# xr_vco_pots_V2.net
KiCad netlist of a schematic drawn in EAGLE
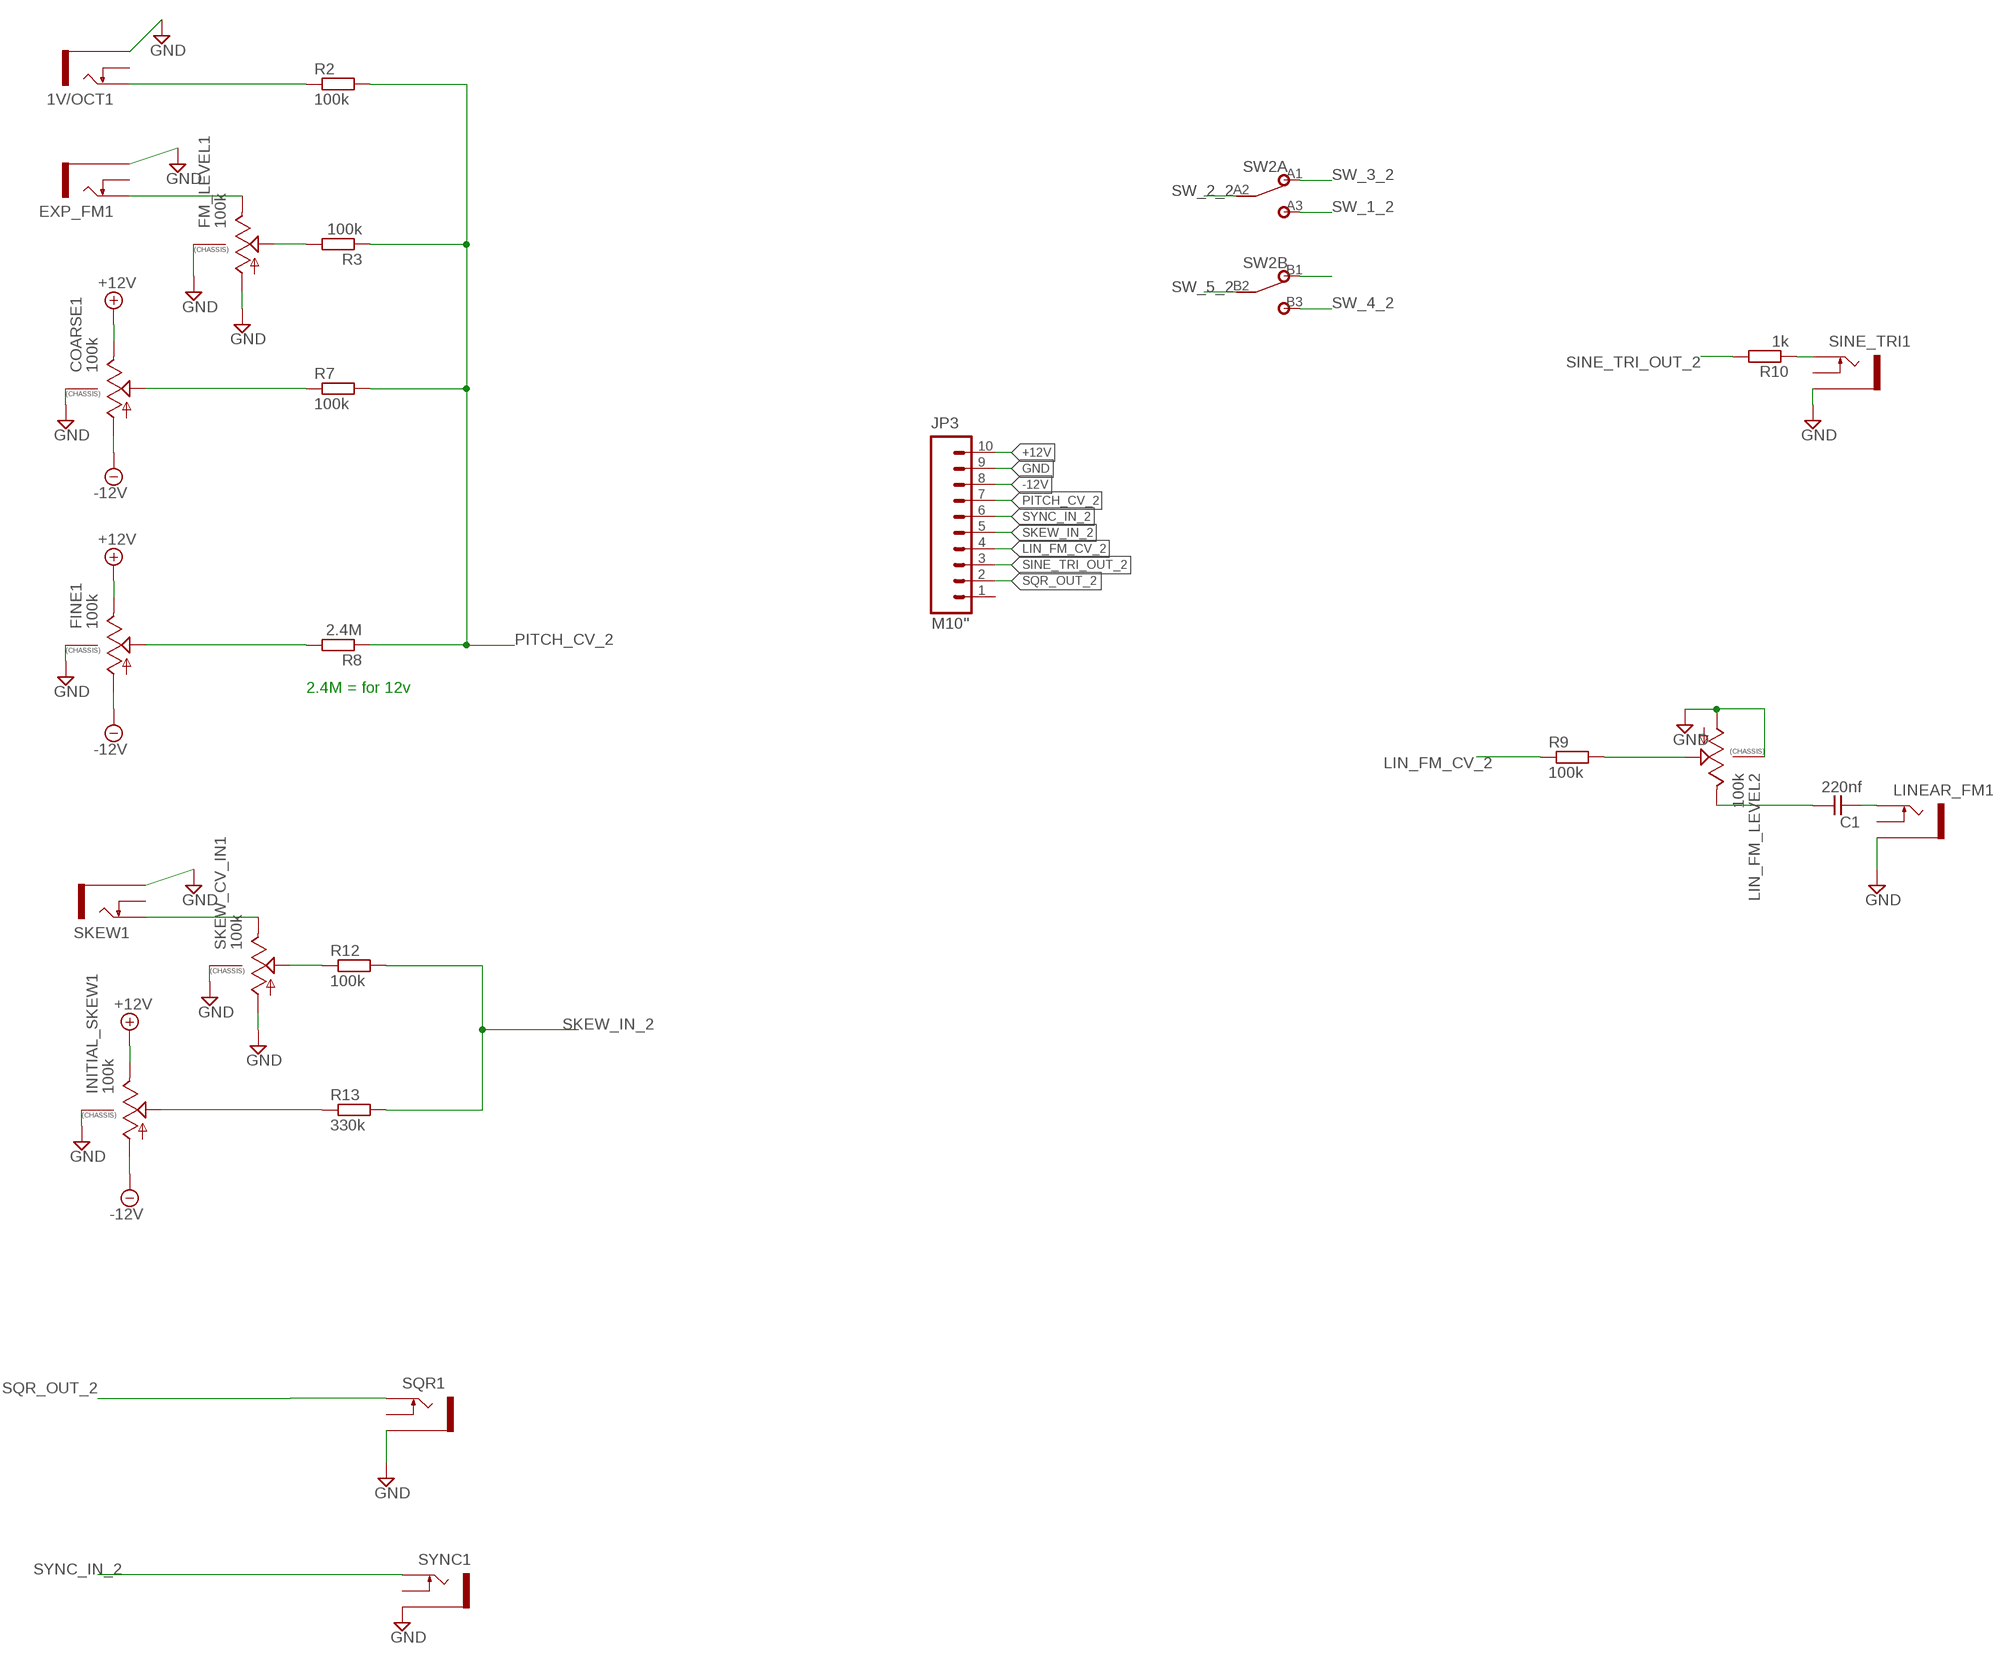
[diagram p0: schematic, sheet 1, part 1 of 2]
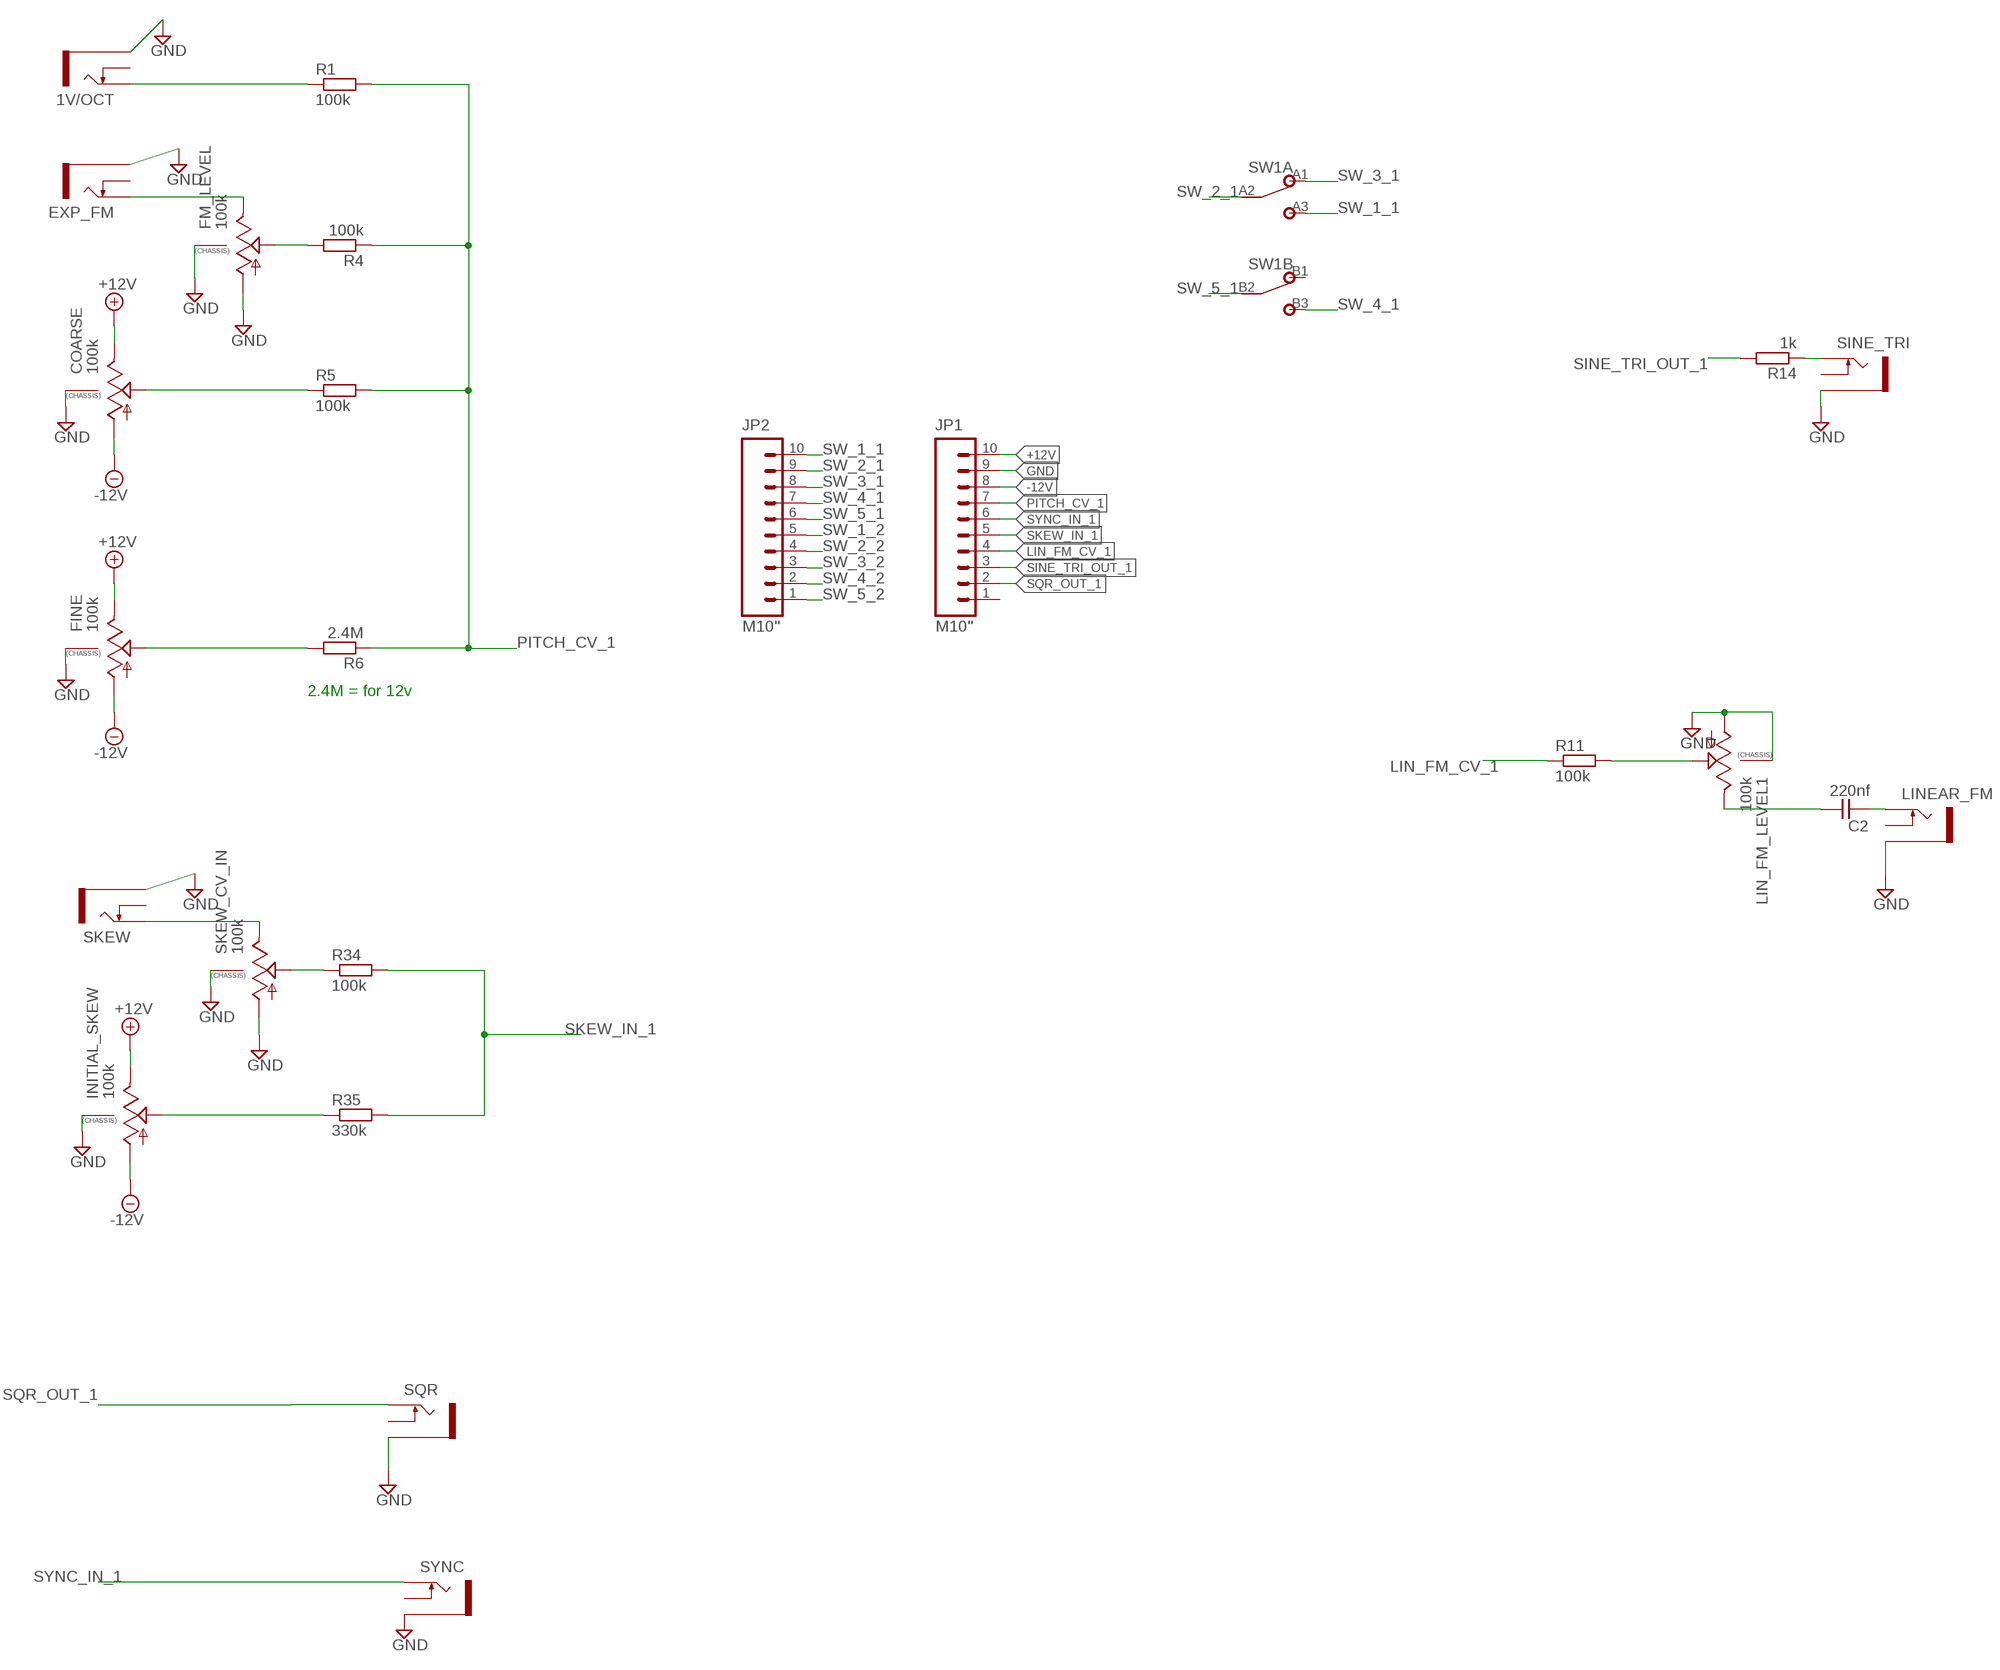
[diagram p1: schematic, sheet 1, part 2 of 2]

(export (version "E")
  (design (tool "Eeschema 10.0.6"))
  (components
    (comp (ref "1V/OCT")
      (value "THONKICONNNEW")
      (footprint "eagle-import:WQP-PJ301M-12_JACK")
      (libsource (lib "eagle-import") (part "THONKICONNNEW"))
    )
    (comp (ref "1V/OCT1")
      (value "THONKICONNNEW")
      (footprint "eagle-import:WQP-PJ301M-12_JACK")
      (libsource (lib "eagle-import") (part "THONKICONNNEW"))
    )
    (comp (ref "C1")
      (value "220nf")
      (footprint "eagle-import:C050-024X044")
      (libsource (lib "eagle-import") (part "C-EU050-024X044"))
    )
    (comp (ref "C2")
      (value "220nf")
      (footprint "eagle-import:C050-024X044")
      (libsource (lib "eagle-import") (part "C-EU050-024X044"))
    )
    (comp (ref "COARSE")
      (value "100k")
      (footprint "eagle-import:9MM_SNAP-IN_POT")
      (libsource (lib "eagle-import") (part "9MM_SNAP-IN_POT_CHASSIS"))
    )
    (comp (ref "COARSE1")
      (value "100k")
      (footprint "eagle-import:9MM_SNAP-IN_POT")
      (libsource (lib "eagle-import") (part "9MM_SNAP-IN_POT_CHASSIS"))
    )
    (comp (ref "EXP_FM")
      (value "THONKICONNNEW")
      (footprint "eagle-import:WQP-PJ301M-12_JACK")
      (libsource (lib "eagle-import") (part "THONKICONNNEW"))
    )
    (comp (ref "EXP_FM1")
      (value "THONKICONNNEW")
      (footprint "eagle-import:WQP-PJ301M-12_JACK")
      (libsource (lib "eagle-import") (part "THONKICONNNEW"))
    )
    (comp (ref "FINE")
      (value "100k")
      (footprint "eagle-import:9MM_SNAP-IN_POT")
      (libsource (lib "eagle-import") (part "9MM_SNAP-IN_POT_CHASSIS"))
    )
    (comp (ref "FINE1")
      (value "100k")
      (footprint "eagle-import:9MM_SNAP-IN_POT")
      (libsource (lib "eagle-import") (part "9MM_SNAP-IN_POT_CHASSIS"))
    )
    (comp (ref "FM_LEVEL")
      (value "100k")
      (footprint "eagle-import:9MM_SNAP-IN_POT")
      (libsource (lib "eagle-import") (part "9MM_SNAP-IN_POT_CHASSIS"))
    )
    (comp (ref "FM_LEVEL1")
      (value "100k")
      (footprint "eagle-import:9MM_SNAP-IN_POT")
      (libsource (lib "eagle-import") (part "9MM_SNAP-IN_POT_CHASSIS"))
    )
    (comp (ref "INITIAL_SKEW")
      (value "100k")
      (footprint "eagle-import:9MM_SNAP-IN_POT")
      (libsource (lib "eagle-import") (part "9MM_SNAP-IN_POT_CHASSIS"))
    )
    (comp (ref "INITIAL_SKEW1")
      (value "100k")
      (footprint "eagle-import:9MM_SNAP-IN_POT")
      (libsource (lib "eagle-import") (part "9MM_SNAP-IN_POT_CHASSIS"))
    )
    (comp (ref "JP1")
      (value "M10\"")
      (footprint "eagle-import:1X10")
      (libsource (lib "eagle-import") (part "M10{dblquote}"))
    )
    (comp (ref "JP2")
      (value "M10\"")
      (footprint "eagle-import:1X10")
      (libsource (lib "eagle-import") (part "M10{dblquote}"))
    )
    (comp (ref "JP3")
      (value "M10\"")
      (footprint "eagle-import:1X10")
      (libsource (lib "eagle-import") (part "M10{dblquote}"))
    )
    (comp (ref "LINEAR_FM")
      (value "THONKICONNNEW")
      (footprint "eagle-import:WQP-PJ301M-12_JACK")
      (libsource (lib "eagle-import") (part "THONKICONNNEW"))
    )
    (comp (ref "LINEAR_FM1")
      (value "THONKICONNNEW")
      (footprint "eagle-import:WQP-PJ301M-12_JACK")
      (libsource (lib "eagle-import") (part "THONKICONNNEW"))
    )
    (comp (ref "LIN_FM_LEVEL1")
      (value "100k")
      (footprint "eagle-import:9MM_SNAP-IN_POT")
      (libsource (lib "eagle-import") (part "9MM_SNAP-IN_POT_CHASSIS"))
    )
    (comp (ref "LIN_FM_LEVEL2")
      (value "100k")
      (footprint "eagle-import:9MM_SNAP-IN_POT")
      (libsource (lib "eagle-import") (part "9MM_SNAP-IN_POT_CHASSIS"))
    )
    (comp (ref "R1")
      (value "100k")
      (footprint "eagle-import:7MM_RESISTOR")
      (libsource (lib "eagle-import") (part "RESISTOR7MM"))
    )
    (comp (ref "R2")
      (value "100k")
      (footprint "eagle-import:7MM_RESISTOR")
      (libsource (lib "eagle-import") (part "RESISTOR7MM"))
    )
    (comp (ref "R3")
      (value "100k")
      (footprint "eagle-import:7MM_RESISTOR")
      (libsource (lib "eagle-import") (part "RESISTOR7MM"))
    )
    (comp (ref "R4")
      (value "100k")
      (footprint "eagle-import:7MM_RESISTOR")
      (libsource (lib "eagle-import") (part "RESISTOR7MM"))
    )
    (comp (ref "R5")
      (value "100k")
      (footprint "eagle-import:7MM_RESISTOR")
      (libsource (lib "eagle-import") (part "RESISTOR7MM"))
    )
    (comp (ref "R6")
      (value "2.4M")
      (footprint "eagle-import:7MM_RESISTOR")
      (libsource (lib "eagle-import") (part "RESISTOR7MM"))
    )
    (comp (ref "R7")
      (value "100k")
      (footprint "eagle-import:7MM_RESISTOR")
      (libsource (lib "eagle-import") (part "RESISTOR7MM"))
    )
    (comp (ref "R8")
      (value "2.4M")
      (footprint "eagle-import:7MM_RESISTOR")
      (libsource (lib "eagle-import") (part "RESISTOR7MM"))
    )
    (comp (ref "R9")
      (value "100k")
      (footprint "eagle-import:7MM_RESISTOR")
      (libsource (lib "eagle-import") (part "RESISTOR7MM"))
    )
    (comp (ref "R10")
      (value "1k")
      (footprint "eagle-import:7MM_RESISTOR")
      (libsource (lib "eagle-import") (part "RESISTOR7MM"))
    )
    (comp (ref "R11")
      (value "100k")
      (footprint "eagle-import:7MM_RESISTOR")
      (libsource (lib "eagle-import") (part "RESISTOR7MM"))
    )
    (comp (ref "R12")
      (value "100k")
      (footprint "eagle-import:7MM_RESISTOR")
      (libsource (lib "eagle-import") (part "RESISTOR7MM"))
    )
    (comp (ref "R13")
      (value "330k")
      (footprint "eagle-import:7MM_RESISTOR")
      (libsource (lib "eagle-import") (part "RESISTOR7MM"))
    )
    (comp (ref "R14")
      (value "1k")
      (footprint "eagle-import:7MM_RESISTOR")
      (libsource (lib "eagle-import") (part "RESISTOR7MM"))
    )
    (comp (ref "R34")
      (value "100k")
      (footprint "eagle-import:7MM_RESISTOR")
      (libsource (lib "eagle-import") (part "RESISTOR7MM"))
    )
    (comp (ref "R35")
      (value "330k")
      (footprint "eagle-import:7MM_RESISTOR")
      (libsource (lib "eagle-import") (part "RESISTOR7MM"))
    )
    (comp (ref "SINE_TRI")
      (value "THONKICONNNEW")
      (footprint "eagle-import:WQP-PJ301M-12_JACK")
      (libsource (lib "eagle-import") (part "THONKICONNNEW"))
    )
    (comp (ref "SINE_TRI1")
      (value "THONKICONNNEW")
      (footprint "eagle-import:WQP-PJ301M-12_JACK")
      (libsource (lib "eagle-import") (part "THONKICONNNEW"))
    )
    (comp (ref "SKEW")
      (value "THONKICONNNEW")
      (footprint "eagle-import:WQP-PJ301M-12_JACK")
      (libsource (lib "eagle-import") (part "THONKICONNNEW"))
    )
    (comp (ref "SKEW1")
      (value "THONKICONNNEW")
      (footprint "eagle-import:WQP-PJ301M-12_JACK")
      (libsource (lib "eagle-import") (part "THONKICONNNEW"))
    )
    (comp (ref "SKEW_CV_IN")
      (value "100k")
      (footprint "eagle-import:9MM_SNAP-IN_POT")
      (libsource (lib "eagle-import") (part "9MM_SNAP-IN_POT_CHASSIS"))
    )
    (comp (ref "SKEW_CV_IN1")
      (value "100k")
      (footprint "eagle-import:9MM_SNAP-IN_POT")
      (libsource (lib "eagle-import") (part "9MM_SNAP-IN_POT_CHASSIS"))
    )
    (comp (ref "SQR")
      (value "THONKICONNNEW")
      (footprint "eagle-import:WQP-PJ301M-12_JACK")
      (libsource (lib "eagle-import") (part "THONKICONNNEW"))
    )
    (comp (ref "SQR1")
      (value "THONKICONNNEW")
      (footprint "eagle-import:WQP-PJ301M-12_JACK")
      (libsource (lib "eagle-import") (part "THONKICONNNEW"))
    )
    (comp (ref "SW1")
      (value "DPDT")
      (footprint "eagle-import:DPDT")
      (libsource (lib "eagle-import") (part "DPDT"))
    )
    (comp (ref "SW2")
      (value "DPDT")
      (footprint "eagle-import:DPDT")
      (libsource (lib "eagle-import") (part "DPDT"))
    )
    (comp (ref "SYNC")
      (value "THONKICONNNEW")
      (footprint "eagle-import:WQP-PJ301M-12_JACK")
      (libsource (lib "eagle-import") (part "THONKICONNNEW"))
    )
    (comp (ref "SYNC1")
      (value "THONKICONNNEW")
      (footprint "eagle-import:WQP-PJ301M-12_JACK")
      (libsource (lib "eagle-import") (part "THONKICONNNEW"))
    )
  )
  (nets
    (net (code "1") (name "+12V") (class "Default")
      (node (ref "COARSE") (pin "3") (pinfunction "E_3") (pintype "passive"))
      (node (ref "COARSE1") (pin "3") (pinfunction "E_3") (pintype "passive"))
      (node (ref "FINE") (pin "3") (pinfunction "E_3") (pintype "passive"))
      (node (ref "FINE1") (pin "3") (pinfunction "E_3") (pintype "passive"))
      (node (ref "INITIAL_SKEW") (pin "3") (pinfunction "E_3") (pintype "passive"))
      (node (ref "INITIAL_SKEW1") (pin "3") (pinfunction "E_3") (pintype "passive"))
      (node (ref "JP1") (pin "10") (pinfunction "10_10") (pintype "passive"))
      (node (ref "JP3") (pin "10") (pinfunction "10_10") (pintype "passive"))
    )
    (net (code "2") (name "-12V") (class "Default")
      (node (ref "COARSE") (pin "1") (pinfunction "A_1") (pintype "passive"))
      (node (ref "COARSE1") (pin "1") (pinfunction "A_1") (pintype "passive"))
      (node (ref "FINE") (pin "1") (pinfunction "A_1") (pintype "passive"))
      (node (ref "FINE1") (pin "1") (pinfunction "A_1") (pintype "passive"))
      (node (ref "INITIAL_SKEW") (pin "1") (pinfunction "A_1") (pintype "passive"))
      (node (ref "INITIAL_SKEW1") (pin "1") (pinfunction "A_1") (pintype "passive"))
      (node (ref "JP1") (pin "8") (pinfunction "8_8") (pintype "passive"))
      (node (ref "JP3") (pin "8") (pinfunction "8_8") (pintype "passive"))
    )
    (net (code "3") (name "/SW_1_1") (class "Default")
      (node (ref "JP2") (pin "10") (pinfunction "10_10") (pintype "passive"))
      (node (ref "SW1") (pin "A3") (pinfunction "3_A3") (pintype "passive"))
    )
    (net (code "4") (name "/SW_1_2") (class "Default")
      (node (ref "JP2") (pin "5") (pinfunction "5_5") (pintype "passive"))
      (node (ref "SW2") (pin "A3") (pinfunction "3_A3") (pintype "passive"))
    )
    (net (code "5") (name "/SW_2_1") (class "Default")
      (node (ref "JP2") (pin "9") (pinfunction "9_9") (pintype "passive"))
      (node (ref "SW1") (pin "A2") (pinfunction "2_A2") (pintype "passive"))
    )
    (net (code "6") (name "/SW_2_2") (class "Default")
      (node (ref "JP2") (pin "4") (pinfunction "4_4") (pintype "passive"))
      (node (ref "SW2") (pin "A2") (pinfunction "2_A2") (pintype "passive"))
    )
    (net (code "7") (name "/SW_3_1") (class "Default")
      (node (ref "JP2") (pin "8") (pinfunction "8_8") (pintype "passive"))
      (node (ref "SW1") (pin "A1") (pinfunction "1_A1") (pintype "passive"))
    )
    (net (code "8") (name "/SW_3_2") (class "Default")
      (node (ref "JP2") (pin "3") (pinfunction "3_3") (pintype "passive"))
      (node (ref "SW2") (pin "A1") (pinfunction "1_A1") (pintype "passive"))
    )
    (net (code "9") (name "/SW_4_1") (class "Default")
      (node (ref "JP2") (pin "7") (pinfunction "7_7") (pintype "passive"))
      (node (ref "SW1") (pin "B3") (pinfunction "3_B3") (pintype "passive"))
    )
    (net (code "10") (name "/SW_4_2") (class "Default")
      (node (ref "JP2") (pin "2") (pinfunction "2_2") (pintype "passive"))
      (node (ref "SW2") (pin "B3") (pinfunction "3_B3") (pintype "passive"))
    )
    (net (code "11") (name "/SW_5_1") (class "Default")
      (node (ref "JP2") (pin "6") (pinfunction "6_6") (pintype "passive"))
      (node (ref "SW1") (pin "B2") (pinfunction "2_B2") (pintype "passive"))
    )
    (net (code "12") (name "/SW_5_2") (class "Default")
      (node (ref "JP2") (pin "1") (pinfunction "1_1") (pintype "passive"))
      (node (ref "SW2") (pin "B2") (pinfunction "2_B2") (pintype "passive"))
    )
    (net (code "13") (name "GND") (class "Default")
      (node (ref "1V/OCT") (pin "P$3_SLEEVE") (pinfunction "SLEEVE_P$3_SLEEVE") (pintype "passive"))
      (node (ref "1V/OCT1") (pin "P$3_SLEEVE") (pinfunction "SLEEVE_P$3_SLEEVE") (pintype "passive"))
      (node (ref "COARSE") (pin "CHASSIS2") (pinfunction "P$1_CHASSIS2") (pintype "passive"))
      (node (ref "COARSE1") (pin "CHASSIS2") (pinfunction "P$1_CHASSIS2") (pintype "passive"))
      (node (ref "EXP_FM") (pin "P$3_SLEEVE") (pinfunction "SLEEVE_P$3_SLEEVE") (pintype "passive"))
      (node (ref "EXP_FM1") (pin "P$3_SLEEVE") (pinfunction "SLEEVE_P$3_SLEEVE") (pintype "passive"))
      (node (ref "FINE") (pin "CHASSIS2") (pinfunction "P$1_CHASSIS2") (pintype "passive"))
      (node (ref "FINE1") (pin "CHASSIS2") (pinfunction "P$1_CHASSIS2") (pintype "passive"))
      (node (ref "FM_LEVEL") (pin "1") (pinfunction "A_1") (pintype "passive"))
      (node (ref "FM_LEVEL") (pin "CHASSIS2") (pinfunction "P$1_CHASSIS2") (pintype "passive"))
      (node (ref "FM_LEVEL1") (pin "1") (pinfunction "A_1") (pintype "passive"))
      (node (ref "FM_LEVEL1") (pin "CHASSIS2") (pinfunction "P$1_CHASSIS2") (pintype "passive"))
      (node (ref "INITIAL_SKEW") (pin "CHASSIS2") (pinfunction "P$1_CHASSIS2") (pintype "passive"))
      (node (ref "INITIAL_SKEW1") (pin "CHASSIS2") (pinfunction "P$1_CHASSIS2") (pintype "passive"))
      (node (ref "JP1") (pin "9") (pinfunction "9_9") (pintype "passive"))
      (node (ref "JP3") (pin "9") (pinfunction "9_9") (pintype "passive"))
      (node (ref "LINEAR_FM") (pin "P$3_SLEEVE") (pinfunction "SLEEVE_P$3_SLEEVE") (pintype "passive"))
      (node (ref "LINEAR_FM1") (pin "P$3_SLEEVE") (pinfunction "SLEEVE_P$3_SLEEVE") (pintype "passive"))
      (node (ref "LIN_FM_LEVEL1") (pin "1") (pinfunction "A_1") (pintype "passive"))
      (node (ref "LIN_FM_LEVEL1") (pin "CHASSIS2") (pinfunction "P$1_CHASSIS2") (pintype "passive"))
      (node (ref "LIN_FM_LEVEL2") (pin "1") (pinfunction "A_1") (pintype "passive"))
      (node (ref "LIN_FM_LEVEL2") (pin "CHASSIS2") (pinfunction "P$1_CHASSIS2") (pintype "passive"))
      (node (ref "SINE_TRI") (pin "P$3_SLEEVE") (pinfunction "SLEEVE_P$3_SLEEVE") (pintype "passive"))
      (node (ref "SINE_TRI1") (pin "P$3_SLEEVE") (pinfunction "SLEEVE_P$3_SLEEVE") (pintype "passive"))
      (node (ref "SKEW") (pin "P$3_SLEEVE") (pinfunction "SLEEVE_P$3_SLEEVE") (pintype "passive"))
      (node (ref "SKEW1") (pin "P$3_SLEEVE") (pinfunction "SLEEVE_P$3_SLEEVE") (pintype "passive"))
      (node (ref "SKEW_CV_IN") (pin "1") (pinfunction "A_1") (pintype "passive"))
      (node (ref "SKEW_CV_IN") (pin "CHASSIS2") (pinfunction "P$1_CHASSIS2") (pintype "passive"))
      (node (ref "SKEW_CV_IN1") (pin "1") (pinfunction "A_1") (pintype "passive"))
      (node (ref "SKEW_CV_IN1") (pin "CHASSIS2") (pinfunction "P$1_CHASSIS2") (pintype "passive"))
      (node (ref "SQR") (pin "P$3_SLEEVE") (pinfunction "SLEEVE_P$3_SLEEVE") (pintype "passive"))
      (node (ref "SQR1") (pin "P$3_SLEEVE") (pinfunction "SLEEVE_P$3_SLEEVE") (pintype "passive"))
      (node (ref "SYNC") (pin "P$3_SLEEVE") (pinfunction "SLEEVE_P$3_SLEEVE") (pintype "passive"))
      (node (ref "SYNC1") (pin "P$3_SLEEVE") (pinfunction "SLEEVE_P$3_SLEEVE") (pintype "passive"))
    )
    (net (code "14") (name "LIN_FM_CV_1") (class "Default")
      (node (ref "JP1") (pin "4") (pinfunction "4_4") (pintype "passive"))
      (node (ref "R11") (pin "1") (pinfunction "1_1") (pintype "passive"))
    )
    (net (code "15") (name "LIN_FM_CV_2") (class "Default")
      (node (ref "JP3") (pin "4") (pinfunction "4_4") (pintype "passive"))
      (node (ref "R9") (pin "1") (pinfunction "1_1") (pintype "passive"))
    )
    (net (code "16") (name "Net-(1V/OCT-TIP)") (class "Default")
      (node (ref "1V/OCT") (pin "P$1_TIP") (pinfunction "TIP_P$1_TIP") (pintype "passive"))
      (node (ref "R1") (pin "1") (pinfunction "1_1") (pintype "passive"))
    )
    (net (code "17") (name "Net-(1V/OCT1-TIP)") (class "Default")
      (node (ref "1V/OCT1") (pin "P$1_TIP") (pinfunction "TIP_P$1_TIP") (pintype "passive"))
      (node (ref "R2") (pin "1") (pinfunction "1_1") (pintype "passive"))
    )
    (net (code "18") (name "Net-(COARSE-S)") (class "Default")
      (node (ref "COARSE") (pin "2") (pinfunction "S_2") (pintype "passive"))
      (node (ref "R5") (pin "1") (pinfunction "1_1") (pintype "passive"))
    )
    (net (code "19") (name "Net-(COARSE1-S)") (class "Default")
      (node (ref "COARSE1") (pin "2") (pinfunction "S_2") (pintype "passive"))
      (node (ref "R7") (pin "1") (pinfunction "1_1") (pintype "passive"))
    )
    (net (code "20") (name "Net-(EXP_FM-TIP)") (class "Default")
      (node (ref "EXP_FM") (pin "P$1_TIP") (pinfunction "TIP_P$1_TIP") (pintype "passive"))
      (node (ref "FM_LEVEL") (pin "3") (pinfunction "E_3") (pintype "passive"))
    )
    (net (code "21") (name "Net-(EXP_FM1-TIP)") (class "Default")
      (node (ref "EXP_FM1") (pin "P$1_TIP") (pinfunction "TIP_P$1_TIP") (pintype "passive"))
      (node (ref "FM_LEVEL1") (pin "3") (pinfunction "E_3") (pintype "passive"))
    )
    (net (code "22") (name "Net-(FINE-S)") (class "Default")
      (node (ref "FINE") (pin "2") (pinfunction "S_2") (pintype "passive"))
      (node (ref "R6") (pin "2") (pinfunction "2_2") (pintype "passive"))
    )
    (net (code "23") (name "Net-(FINE1-S)") (class "Default")
      (node (ref "FINE1") (pin "2") (pinfunction "S_2") (pintype "passive"))
      (node (ref "R8") (pin "2") (pinfunction "2_2") (pintype "passive"))
    )
    (net (code "24") (name "Net-(FM_LEVEL-S)") (class "Default")
      (node (ref "FM_LEVEL") (pin "2") (pinfunction "S_2") (pintype "passive"))
      (node (ref "R4") (pin "2") (pinfunction "2_2") (pintype "passive"))
    )
    (net (code "25") (name "Net-(FM_LEVEL1-S)") (class "Default")
      (node (ref "FM_LEVEL1") (pin "2") (pinfunction "S_2") (pintype "passive"))
      (node (ref "R3") (pin "2") (pinfunction "2_2") (pintype "passive"))
    )
    (net (code "26") (name "Net-(INITIAL_SKEW-S)") (class "Default")
      (node (ref "INITIAL_SKEW") (pin "2") (pinfunction "S_2") (pintype "passive"))
      (node (ref "R35") (pin "1") (pinfunction "1_1") (pintype "passive"))
    )
    (net (code "27") (name "Net-(INITIAL_SKEW1-S)") (class "Default")
      (node (ref "INITIAL_SKEW1") (pin "2") (pinfunction "S_2") (pintype "passive"))
      (node (ref "R13") (pin "1") (pinfunction "1_1") (pintype "passive"))
    )
    (net (code "28") (name "Net-(LINEAR_FM-TIP)") (class "Default")
      (node (ref "C2") (pin "2") (pinfunction "2_2") (pintype "passive"))
      (node (ref "LINEAR_FM") (pin "P$1_TIP") (pinfunction "TIP_P$1_TIP") (pintype "passive"))
    )
    (net (code "29") (name "Net-(LINEAR_FM1-TIP)") (class "Default")
      (node (ref "C1") (pin "2") (pinfunction "2_2") (pintype "passive"))
      (node (ref "LINEAR_FM1") (pin "P$1_TIP") (pinfunction "TIP_P$1_TIP") (pintype "passive"))
    )
    (net (code "30") (name "Net-(LIN_FM_LEVEL1-E)") (class "Default")
      (node (ref "C2") (pin "1") (pinfunction "1_1") (pintype "passive"))
      (node (ref "LIN_FM_LEVEL1") (pin "3") (pinfunction "E_3") (pintype "passive"))
    )
    (net (code "31") (name "Net-(LIN_FM_LEVEL1-S)") (class "Default")
      (node (ref "LIN_FM_LEVEL1") (pin "2") (pinfunction "S_2") (pintype "passive"))
      (node (ref "R11") (pin "2") (pinfunction "2_2") (pintype "passive"))
    )
    (net (code "32") (name "Net-(LIN_FM_LEVEL2-E)") (class "Default")
      (node (ref "C1") (pin "1") (pinfunction "1_1") (pintype "passive"))
      (node (ref "LIN_FM_LEVEL2") (pin "3") (pinfunction "E_3") (pintype "passive"))
    )
    (net (code "33") (name "Net-(LIN_FM_LEVEL2-S)") (class "Default")
      (node (ref "LIN_FM_LEVEL2") (pin "2") (pinfunction "S_2") (pintype "passive"))
      (node (ref "R9") (pin "2") (pinfunction "2_2") (pintype "passive"))
    )
    (net (code "34") (name "Net-(SINE_TRI-TIP)") (class "Default")
      (node (ref "R14") (pin "1") (pinfunction "1_1") (pintype "passive"))
      (node (ref "SINE_TRI") (pin "P$1_TIP") (pinfunction "TIP_P$1_TIP") (pintype "passive"))
    )
    (net (code "35") (name "Net-(SINE_TRI1-TIP)") (class "Default")
      (node (ref "R10") (pin "1") (pinfunction "1_1") (pintype "passive"))
      (node (ref "SINE_TRI1") (pin "P$1_TIP") (pinfunction "TIP_P$1_TIP") (pintype "passive"))
    )
    (net (code "36") (name "Net-(SKEW-TIP)") (class "Default")
      (node (ref "SKEW") (pin "P$1_TIP") (pinfunction "TIP_P$1_TIP") (pintype "passive"))
      (node (ref "SKEW_CV_IN") (pin "3") (pinfunction "E_3") (pintype "passive"))
    )
    (net (code "37") (name "Net-(SKEW1-TIP)") (class "Default")
      (node (ref "SKEW1") (pin "P$1_TIP") (pinfunction "TIP_P$1_TIP") (pintype "passive"))
      (node (ref "SKEW_CV_IN1") (pin "3") (pinfunction "E_3") (pintype "passive"))
    )
    (net (code "38") (name "Net-(SKEW_CV_IN-S)") (class "Default")
      (node (ref "R34") (pin "1") (pinfunction "1_1") (pintype "passive"))
      (node (ref "SKEW_CV_IN") (pin "2") (pinfunction "S_2") (pintype "passive"))
    )
    (net (code "39") (name "Net-(SKEW_CV_IN1-S)") (class "Default")
      (node (ref "R12") (pin "1") (pinfunction "1_1") (pintype "passive"))
      (node (ref "SKEW_CV_IN1") (pin "2") (pinfunction "S_2") (pintype "passive"))
    )
    (net (code "40") (name "PITCH_CV_1") (class "Default")
      (node (ref "JP1") (pin "7") (pinfunction "7_7") (pintype "passive"))
      (node (ref "R1") (pin "2") (pinfunction "2_2") (pintype "passive"))
      (node (ref "R4") (pin "1") (pinfunction "1_1") (pintype "passive"))
      (node (ref "R5") (pin "2") (pinfunction "2_2") (pintype "passive"))
      (node (ref "R6") (pin "1") (pinfunction "1_1") (pintype "passive"))
    )
    (net (code "41") (name "PITCH_CV_2") (class "Default")
      (node (ref "JP3") (pin "7") (pinfunction "7_7") (pintype "passive"))
      (node (ref "R2") (pin "2") (pinfunction "2_2") (pintype "passive"))
      (node (ref "R3") (pin "1") (pinfunction "1_1") (pintype "passive"))
      (node (ref "R7") (pin "2") (pinfunction "2_2") (pintype "passive"))
      (node (ref "R8") (pin "1") (pinfunction "1_1") (pintype "passive"))
    )
    (net (code "42") (name "SINE_TRI_OUT_1") (class "Default")
      (node (ref "JP1") (pin "3") (pinfunction "3_3") (pintype "passive"))
      (node (ref "R14") (pin "2") (pinfunction "2_2") (pintype "passive"))
    )
    (net (code "43") (name "SINE_TRI_OUT_2") (class "Default")
      (node (ref "JP3") (pin "3") (pinfunction "3_3") (pintype "passive"))
      (node (ref "R10") (pin "2") (pinfunction "2_2") (pintype "passive"))
    )
    (net (code "44") (name "SKEW_IN_1") (class "Default")
      (node (ref "JP1") (pin "5") (pinfunction "5_5") (pintype "passive"))
      (node (ref "R34") (pin "2") (pinfunction "2_2") (pintype "passive"))
      (node (ref "R35") (pin "2") (pinfunction "2_2") (pintype "passive"))
    )
    (net (code "45") (name "SKEW_IN_2") (class "Default")
      (node (ref "JP3") (pin "5") (pinfunction "5_5") (pintype "passive"))
      (node (ref "R12") (pin "2") (pinfunction "2_2") (pintype "passive"))
      (node (ref "R13") (pin "2") (pinfunction "2_2") (pintype "passive"))
    )
    (net (code "46") (name "SQR_OUT_1") (class "Default")
      (node (ref "JP1") (pin "2") (pinfunction "2_2") (pintype "passive"))
      (node (ref "SQR") (pin "P$1_TIP") (pinfunction "TIP_P$1_TIP") (pintype "passive"))
    )
    (net (code "47") (name "SQR_OUT_2") (class "Default")
      (node (ref "JP3") (pin "2") (pinfunction "2_2") (pintype "passive"))
      (node (ref "SQR1") (pin "P$1_TIP") (pinfunction "TIP_P$1_TIP") (pintype "passive"))
    )
    (net (code "48") (name "SYNC_IN_1") (class "Default")
      (node (ref "JP1") (pin "6") (pinfunction "6_6") (pintype "passive"))
      (node (ref "SYNC") (pin "P$1_TIP") (pinfunction "TIP_P$1_TIP") (pintype "passive"))
    )
    (net (code "49") (name "SYNC_IN_2") (class "Default")
      (node (ref "JP3") (pin "6") (pinfunction "6_6") (pintype "passive"))
      (node (ref "SYNC1") (pin "P$1_TIP") (pinfunction "TIP_P$1_TIP") (pintype "passive"))
    )
    (net (code "50") (name "unconnected-(1V/OCT-SWITCH-PadP$2_SWITCH)") (class "Default")
      (node (ref "1V/OCT") (pin "P$2_SWITCH") (pinfunction "SWITCH_P$2_SWITCH") (pintype "passive"))
    )
    (net (code "51") (name "unconnected-(1V/OCT1-SWITCH-PadP$2_SWITCH)") (class "Default")
      (node (ref "1V/OCT1") (pin "P$2_SWITCH") (pinfunction "SWITCH_P$2_SWITCH") (pintype "passive"))
    )
    (net (code "52") (name "unconnected-(EXP_FM-SWITCH-PadP$2_SWITCH)") (class "Default")
      (node (ref "EXP_FM") (pin "P$2_SWITCH") (pinfunction "SWITCH_P$2_SWITCH") (pintype "passive"))
    )
    (net (code "53") (name "unconnected-(EXP_FM1-SWITCH-PadP$2_SWITCH)") (class "Default")
      (node (ref "EXP_FM1") (pin "P$2_SWITCH") (pinfunction "SWITCH_P$2_SWITCH") (pintype "passive"))
    )
    (net (code "54") (name "unconnected-(JP1-Pad1)") (class "Default")
      (node (ref "JP1") (pin "1") (pinfunction "1_1") (pintype "passive"))
    )
    (net (code "55") (name "unconnected-(JP3-Pad1)") (class "Default")
      (node (ref "JP3") (pin "1") (pinfunction "1_1") (pintype "passive"))
    )
    (net (code "56") (name "unconnected-(LINEAR_FM-SWITCH-PadP$2_SWITCH)") (class "Default")
      (node (ref "LINEAR_FM") (pin "P$2_SWITCH") (pinfunction "SWITCH_P$2_SWITCH") (pintype "passive"))
    )
    (net (code "57") (name "unconnected-(LINEAR_FM1-SWITCH-PadP$2_SWITCH)") (class "Default")
      (node (ref "LINEAR_FM1") (pin "P$2_SWITCH") (pinfunction "SWITCH_P$2_SWITCH") (pintype "passive"))
    )
    (net (code "58") (name "unconnected-(SINE_TRI-SWITCH-PadP$2_SWITCH)") (class "Default")
      (node (ref "SINE_TRI") (pin "P$2_SWITCH") (pinfunction "SWITCH_P$2_SWITCH") (pintype "passive"))
    )
    (net (code "59") (name "unconnected-(SINE_TRI1-SWITCH-PadP$2_SWITCH)") (class "Default")
      (node (ref "SINE_TRI1") (pin "P$2_SWITCH") (pinfunction "SWITCH_P$2_SWITCH") (pintype "passive"))
    )
    (net (code "60") (name "unconnected-(SKEW-SWITCH-PadP$2_SWITCH)") (class "Default")
      (node (ref "SKEW") (pin "P$2_SWITCH") (pinfunction "SWITCH_P$2_SWITCH") (pintype "passive"))
    )
    (net (code "61") (name "unconnected-(SKEW1-SWITCH-PadP$2_SWITCH)") (class "Default")
      (node (ref "SKEW1") (pin "P$2_SWITCH") (pinfunction "SWITCH_P$2_SWITCH") (pintype "passive"))
    )
    (net (code "62") (name "unconnected-(SQR-SWITCH-PadP$2_SWITCH)") (class "Default")
      (node (ref "SQR") (pin "P$2_SWITCH") (pinfunction "SWITCH_P$2_SWITCH") (pintype "passive"))
    )
    (net (code "63") (name "unconnected-(SQR1-SWITCH-PadP$2_SWITCH)") (class "Default")
      (node (ref "SQR1") (pin "P$2_SWITCH") (pinfunction "SWITCH_P$2_SWITCH") (pintype "passive"))
    )
    (net (code "64") (name "unconnected-(SW1B-1-PadB1)") (class "Default")
      (node (ref "SW1") (pin "B1") (pinfunction "1_B1") (pintype "passive"))
    )
    (net (code "65") (name "unconnected-(SW2B-1-PadB1)") (class "Default")
      (node (ref "SW2") (pin "B1") (pinfunction "1_B1") (pintype "passive"))
    )
    (net (code "66") (name "unconnected-(SYNC-SWITCH-PadP$2_SWITCH)") (class "Default")
      (node (ref "SYNC") (pin "P$2_SWITCH") (pinfunction "SWITCH_P$2_SWITCH") (pintype "passive"))
    )
    (net (code "67") (name "unconnected-(SYNC1-SWITCH-PadP$2_SWITCH)") (class "Default")
      (node (ref "SYNC1") (pin "P$2_SWITCH") (pinfunction "SWITCH_P$2_SWITCH") (pintype "passive"))
    )
  )
)
